# Clock_Extension.net
KiCad netlist of a schematic drawn in EAGLE
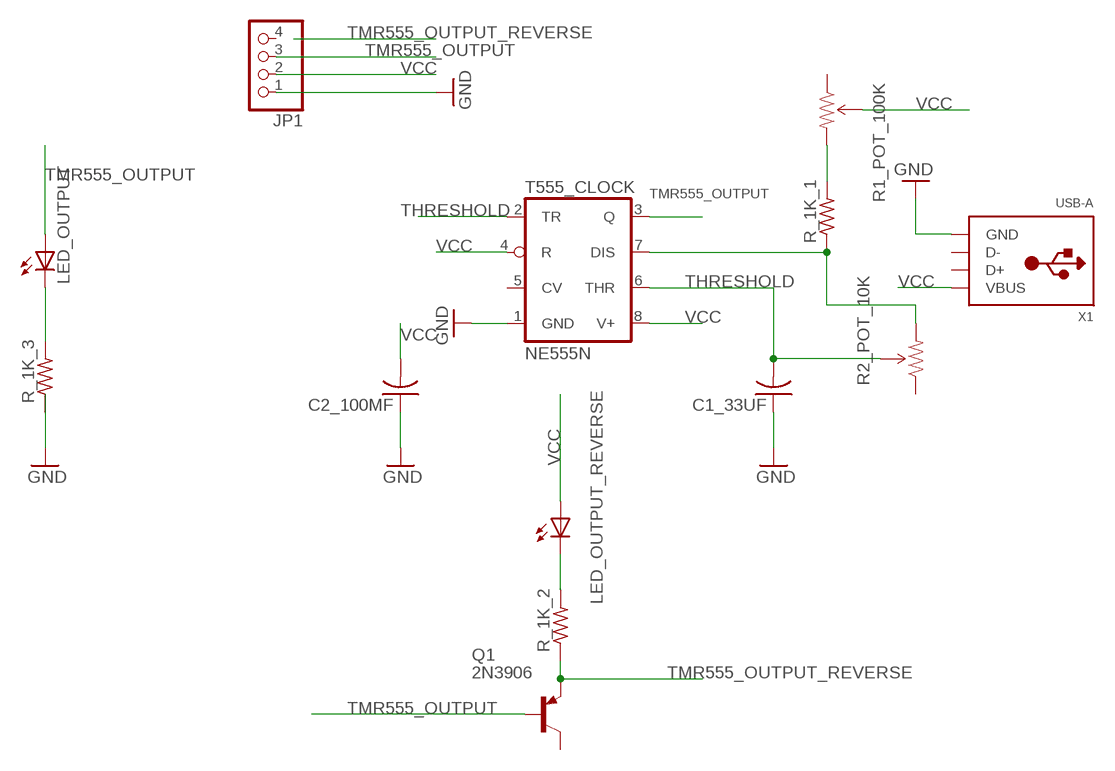
[diagram p0: schematic, sheet 1]

(export (version "E")
  (design (tool "Eeschema 10.0.6"))
  (components
    (comp (ref "C1_33UF")
      (value "C-US025-030X050")
      (footprint "eagle-import:C025-030X050")
      (libsource (lib "eagle-import") (part "C-US025-030X050"))
    )
    (comp (ref "C2_100MF")
      (value "C-US025-030X050")
      (footprint "eagle-import:C025-030X050")
      (libsource (lib "eagle-import") (part "C-US025-030X050"))
    )
    (comp (ref "JP1")
      (value "PINHD-1X4")
      (footprint "eagle-import:1X04")
      (libsource (lib "eagle-import") (part "PINHD-1X4"))
    )
    (comp (ref "LED_OUTPUT")
      (value "LEDSMT1206")
      (footprint "eagle-import:1206")
      (libsource (lib "eagle-import") (part "LEDSMT1206"))
    )
    (comp (ref "LED_OUTPUT_REVERSE")
      (value "LEDSMT1206")
      (footprint "eagle-import:1206")
      (libsource (lib "eagle-import") (part "LEDSMT1206"))
    )
    (comp (ref "Q1")
      (value "2N3906")
      (footprint "eagle-import:TO92")
      (libsource (lib "eagle-import") (part "2N3906"))
    )
    (comp (ref "R1_POT_100K")
      (value "TRIMPOTPTH")
      (footprint "eagle-import:TRIM_POT_PTH")
      (libsource (lib "eagle-import") (part "TRIMPOTPTH"))
    )
    (comp (ref "R2_POT_10K")
      (value "TRIMPOTPTH")
      (footprint "eagle-import:TRIM_POT_PTH")
      (libsource (lib "eagle-import") (part "TRIMPOTPTH"))
    )
    (comp (ref "R_1K_1")
      (value "R-US_R1206")
      (footprint "eagle-import:R1206")
      (libsource (lib "eagle-import") (part "R-US_R1206"))
    )
    (comp (ref "R_1K_2")
      (value "R-US_R1206")
      (footprint "eagle-import:R1206")
      (libsource (lib "eagle-import") (part "R-US_R1206"))
    )
    (comp (ref "R_1K_3")
      (value "R-US_R1206")
      (footprint "eagle-import:R1206")
      (libsource (lib "eagle-import") (part "R-US_R1206"))
    )
    (comp (ref "T555_CLOCK")
      (value "NE555N")
      (footprint "eagle-import:DIL08")
      (libsource (lib "eagle-import") (part "555NNE"))
    )
    (comp (ref "X1")
      (value "USB-A")
      (footprint "eagle-import:MOLEX_480371000")
      (libsource (lib "eagle-import") (part "USB-A"))
    )
  )
  (nets
    (net (code "1") (name "/THRESHOLD") (class "Default")
      (node (ref "C1_33UF") (pin "2") (pinfunction "2_2") (pintype "passive"))
      (node (ref "R2_POT_10K") (pin "2") (pinfunction "WIPER_2") (pintype "passive"))
      (node (ref "T555_CLOCK") (pin "2") (pinfunction "TR_2") (pintype "input"))
      (node (ref "T555_CLOCK") (pin "6") (pinfunction "THR_6") (pintype "input"))
    )
    (net (code "2") (name "/TMR555_OUTPUT") (class "Default")
      (node (ref "JP1") (pin "3") (pinfunction "3_3") (pintype "passive"))
      (node (ref "LED_OUTPUT") (pin "A") (pinfunction "A_A") (pintype "passive"))
      (node (ref "Q1") (pin "2") (pinfunction "B_2") (pintype "passive"))
      (node (ref "T555_CLOCK") (pin "3") (pinfunction "Q_3") (pintype "output"))
    )
    (net (code "3") (name "/TMR555_OUTPUT_REVERSE") (class "Default")
      (node (ref "Q1") (pin "3") (pinfunction "E_3") (pintype "passive"))
      (node (ref "R_1K_2") (pin "1") (pinfunction "1_1") (pintype "passive"))
    )
    (net (code "4") (name "/VCC") (class "Default")
      (node (ref "C2_100MF") (pin "2") (pinfunction "2_2") (pintype "passive"))
      (node (ref "JP1") (pin "2") (pinfunction "2_2") (pintype "passive"))
      (node (ref "LED_OUTPUT_REVERSE") (pin "A") (pinfunction "A_A") (pintype "passive"))
      (node (ref "R1_POT_100K") (pin "2") (pinfunction "WIPER_2") (pintype "passive"))
      (node (ref "T555_CLOCK") (pin "4") (pinfunction "R_4") (pintype "input"))
      (node (ref "T555_CLOCK") (pin "8") (pinfunction "V+_8") (pintype "power_in"))
      (node (ref "X1") (pin "1") (pinfunction "VBUS_1") (pintype "power_in"))
    )
    (net (code "5") (name "GND") (class "Default")
      (node (ref "C1_33UF") (pin "1") (pinfunction "1_1") (pintype "passive"))
      (node (ref "C2_100MF") (pin "1") (pinfunction "1_1") (pintype "passive"))
      (node (ref "JP1") (pin "1") (pinfunction "1_1") (pintype "passive"))
      (node (ref "R_1K_3") (pin "1") (pinfunction "1_1") (pintype "passive"))
      (node (ref "T555_CLOCK") (pin "1") (pinfunction "GND_1") (pintype "power_in"))
      (node (ref "X1") (pin "4") (pinfunction "GND_4") (pintype "power_in"))
    )
    (net (code "6") (name "Net-(LED_OUTPUT-PadC)") (class "Default")
      (node (ref "LED_OUTPUT") (pin "C") (pinfunction "C_C") (pintype "passive"))
      (node (ref "R_1K_3") (pin "2") (pinfunction "2_2") (pintype "passive"))
    )
    (net (code "7") (name "Net-(LED_OUTPUT_REVERSE-PadC)") (class "Default")
      (node (ref "LED_OUTPUT_REVERSE") (pin "C") (pinfunction "C_C") (pintype "passive"))
      (node (ref "R_1K_2") (pin "2") (pinfunction "2_2") (pintype "passive"))
    )
    (net (code "8") (name "Net-(R1_POT_100K-CW)") (class "Default")
      (node (ref "R1_POT_100K") (pin "3") (pinfunction "CW_3") (pintype "passive"))
      (node (ref "R_1K_1") (pin "2") (pinfunction "2_2") (pintype "passive"))
    )
    (net (code "9") (name "Net-(R2_POT_10K-CW)") (class "Default")
      (node (ref "R2_POT_10K") (pin "3") (pinfunction "CW_3") (pintype "passive"))
      (node (ref "R_1K_1") (pin "1") (pinfunction "1_1") (pintype "passive"))
      (node (ref "T555_CLOCK") (pin "7") (pinfunction "DIS_7") (pintype "input"))
    )
    (net (code "10") (name "unconnected-(JP1-Pad4)") (class "Default")
      (node (ref "JP1") (pin "4") (pinfunction "4_4") (pintype "passive"))
    )
    (net (code "11") (name "unconnected-(Q1-C-Pad1)") (class "Default")
      (node (ref "Q1") (pin "1") (pinfunction "C_1") (pintype "passive"))
    )
    (net (code "12") (name "unconnected-(R1_POT_100K-CCW-Pad1)") (class "Default")
      (node (ref "R1_POT_100K") (pin "1") (pinfunction "CCW_1") (pintype "passive"))
    )
    (net (code "13") (name "unconnected-(R2_POT_10K-CCW-Pad1)") (class "Default")
      (node (ref "R2_POT_10K") (pin "1") (pinfunction "CCW_1") (pintype "passive"))
    )
    (net (code "14") (name "unconnected-(T555_CLOCK-CV-Pad5)") (class "Default")
      (node (ref "T555_CLOCK") (pin "5") (pinfunction "CV_5") (pintype "input"))
    )
    (net (code "15") (name "unconnected-(X1-D+-Pad3)") (class "Default")
      (node (ref "X1") (pin "3") (pinfunction "D+_3") (pintype "bidirectional"))
    )
    (net (code "16") (name "unconnected-(X1-D--Pad2)") (class "Default")
      (node (ref "X1") (pin "2") (pinfunction "D-_2") (pintype "bidirectional"))
    )
  )
)
